# T245Controller_rev0.net
KiCad netlist of a schematic drawn in EAGLE
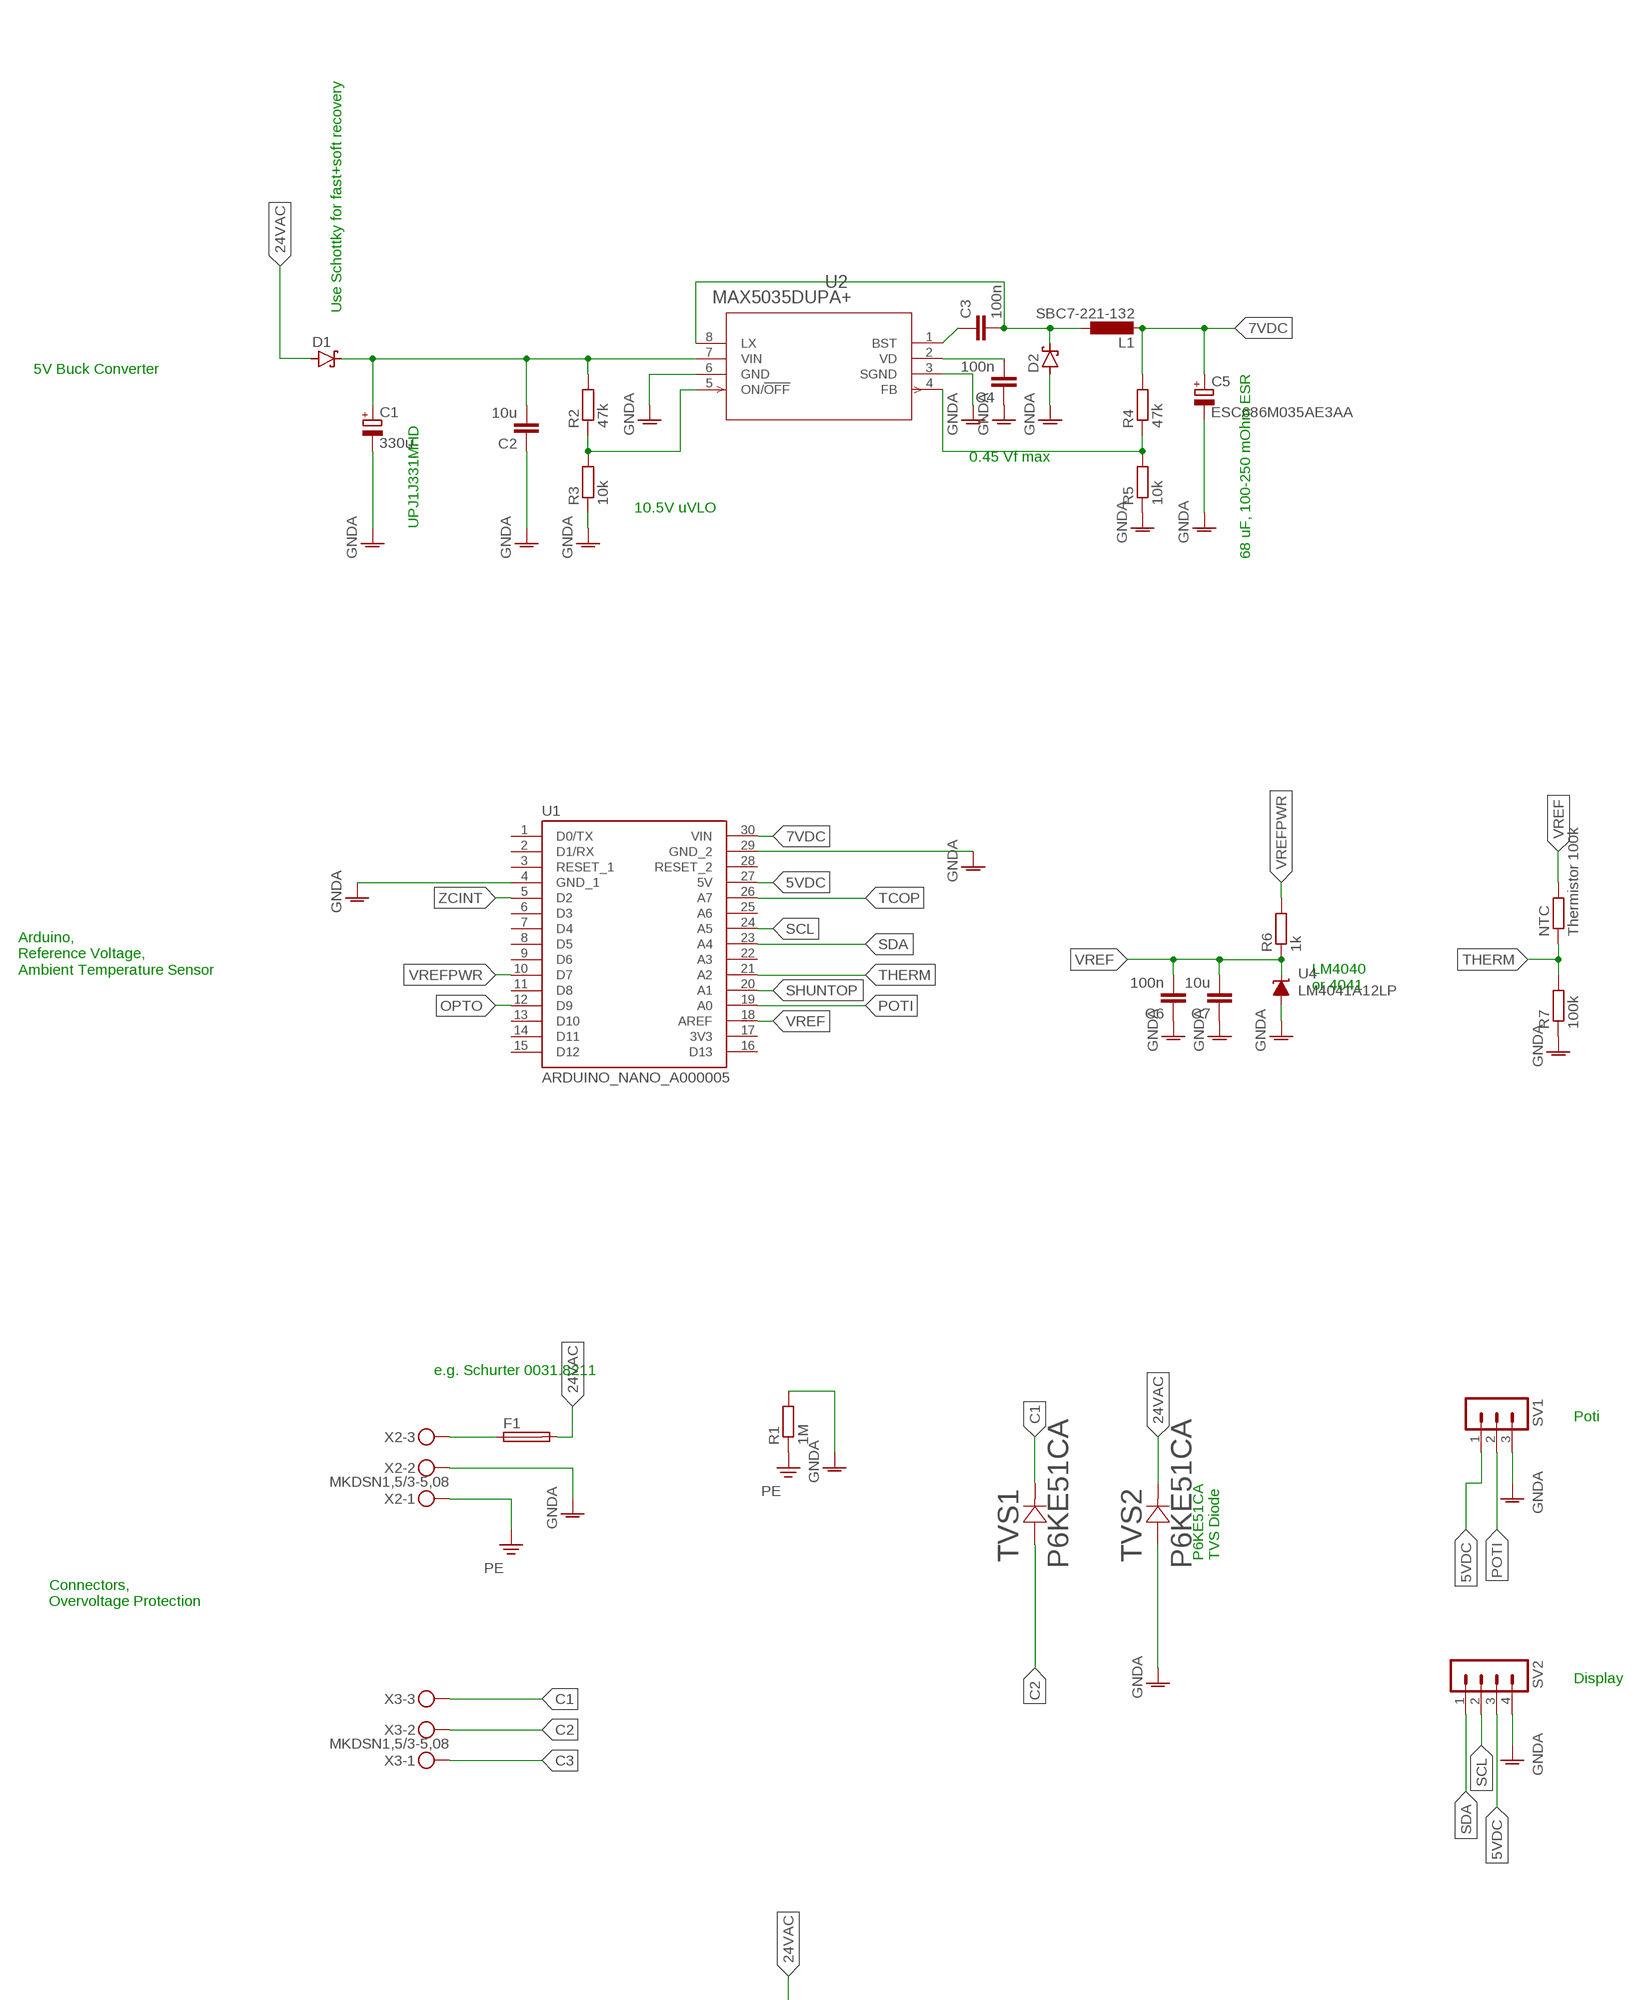
[diagram p0: schematic, sheet 1, part 1 of 2]
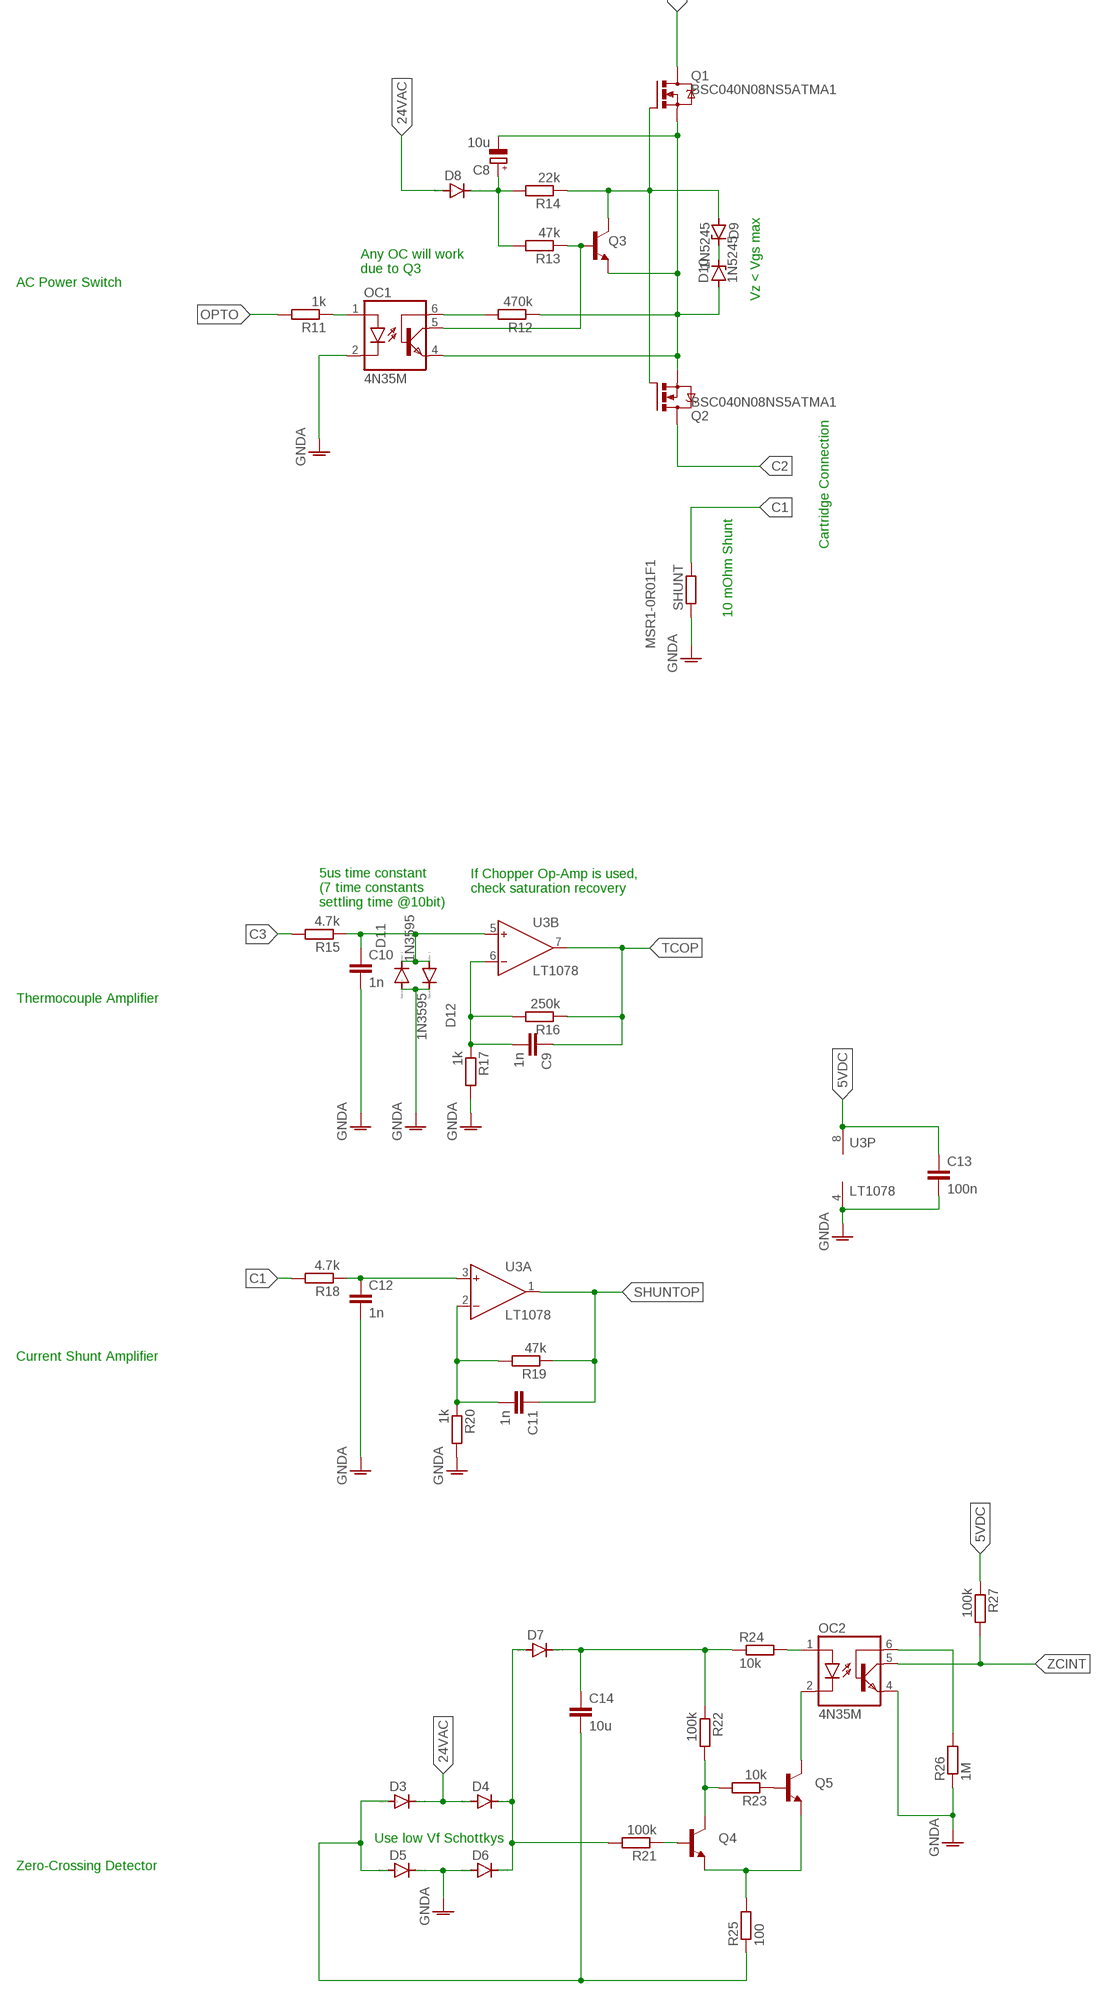
[diagram p1: schematic, sheet 1, part 2 of 2]

(export (version "E")
  (design (tool "Eeschema 10.0.6"))
  (components
    (comp (ref "C1")
      (value "330u")
      (footprint "eagle-import:E5-13")
      (libsource (lib "eagle-import") (part "CPOL-EUE5-13"))
    )
    (comp (ref "C2")
      (value "10u")
      (footprint "eagle-import:C050-024X044")
      (libsource (lib "eagle-import") (part "C-EU050-024X044"))
    )
    (comp (ref "C3")
      (value "100n")
      (footprint "eagle-import:C050-024X044")
      (libsource (lib "eagle-import") (part "C-EU050-024X044"))
    )
    (comp (ref "C4")
      (value "100n")
      (footprint "eagle-import:C050-024X044")
      (libsource (lib "eagle-import") (part "C-EU050-024X044"))
    )
    (comp (ref "C5")
      (value "ESC686M035AE3AA")
      (footprint "eagle-import:E2,5-6")
      (libsource (lib "eagle-import") (part "CPOL-EUE2.5-6"))
    )
    (comp (ref "C6")
      (value "100n")
      (footprint "eagle-import:C050-024X044")
      (libsource (lib "eagle-import") (part "C-EU050-024X044"))
    )
    (comp (ref "C7")
      (value "10u")
      (footprint "eagle-import:C050-024X044")
      (libsource (lib "eagle-import") (part "C-EU050-024X044"))
    )
    (comp (ref "C8")
      (value "10u")
      (footprint "eagle-import:E2,5-6")
      (libsource (lib "eagle-import") (part "CPOL-EUE2.5-6"))
    )
    (comp (ref "C9")
      (value "1n")
      (footprint "eagle-import:C050-024X044")
      (libsource (lib "eagle-import") (part "C-EU050-024X044"))
    )
    (comp (ref "C10")
      (value "1n")
      (footprint "eagle-import:C050-024X044")
      (libsource (lib "eagle-import") (part "C-EU050-024X044"))
    )
    (comp (ref "C11")
      (value "1n")
      (footprint "eagle-import:C050-024X044")
      (libsource (lib "eagle-import") (part "C-EU050-024X044"))
    )
    (comp (ref "C12")
      (value "1n")
      (footprint "eagle-import:C050-024X044")
      (libsource (lib "eagle-import") (part "C-EU050-024X044"))
    )
    (comp (ref "C13")
      (value "100n")
      (footprint "eagle-import:C050-024X044")
      (libsource (lib "eagle-import") (part "C-EU050-024X044"))
    )
    (comp (ref "C14")
      (value "10u")
      (footprint "eagle-import:C050-024X044")
      (libsource (lib "eagle-import") (part "C-EU050-024X044"))
    )
    (comp (ref "D1")
      (value "SCHOTTKY-DIODEF126Z12")
      (footprint "eagle-import:F126Z12")
      (libsource (lib "eagle-import") (part "SCHOTTKY-DIODEF126Z12"))
    )
    (comp (ref "D2")
      (value "SCHOTTKY-DIODEF126Z12")
      (footprint "eagle-import:F126Z12")
      (libsource (lib "eagle-import") (part "SCHOTTKY-DIODEF126Z12"))
    )
    (comp (ref "D3")
      (value "DIODE-D-7.5")
      (footprint "eagle-import:D-7.5")
      (libsource (lib "eagle-import") (part "DIODE-D-7.5"))
    )
    (comp (ref "D4")
      (value "DIODE-D-7.5")
      (footprint "eagle-import:D-7.5")
      (libsource (lib "eagle-import") (part "DIODE-D-7.5"))
    )
    (comp (ref "D5")
      (value "DIODE-D-7.5")
      (footprint "eagle-import:D-7.5")
      (libsource (lib "eagle-import") (part "DIODE-D-7.5"))
    )
    (comp (ref "D6")
      (value "DIODE-D-7.5")
      (footprint "eagle-import:D-7.5")
      (libsource (lib "eagle-import") (part "DIODE-D-7.5"))
    )
    (comp (ref "D7")
      (value "DIODE-D-7.5")
      (footprint "eagle-import:D-7.5")
      (libsource (lib "eagle-import") (part "DIODE-D-7.5"))
    )
    (comp (ref "D8")
      (value "DIODE-D-7.5")
      (footprint "eagle-import:D-7.5")
      (libsource (lib "eagle-import") (part "DIODE-D-7.5"))
    )
    (comp (ref "D9")
      (value "1N5245")
      (footprint "eagle-import:DO41Z10")
      (libsource (lib "eagle-import") (part "ZENER-DIODEDO41Z10"))
    )
    (comp (ref "D10")
      (value "1N5245")
      (footprint "eagle-import:DO41Z10")
      (libsource (lib "eagle-import") (part "ZENER-DIODEDO41Z10"))
    )
    (comp (ref "D11")
      (value "1N3595")
      (footprint "eagle-import:D-7.5")
      (libsource (lib "eagle-import") (part "DIODE-D-7.5"))
    )
    (comp (ref "D12")
      (value "1N3595")
      (footprint "eagle-import:D-7.5")
      (libsource (lib "eagle-import") (part "DIODE-D-7.5"))
    )
    (comp (ref "F1")
      (value "SH22,5A")
      (footprint "eagle-import:SH22,5A")
      (fields (field (name "MPN") "0031.7701.11"))
      (libsource (lib "eagle-import") (part "SH22,5A"))
    )
    (comp (ref "L1")
      (value "SBC7-221-132")
      (footprint "eagle-import:0207_10")
      (libsource (lib "eagle-import") (part "L-EU0207/10"))
    )
    (comp (ref "NTC")
      (value "Thermistor 100k")
      (footprint "eagle-import:0207_10")
      (libsource (lib "eagle-import") (part "rcl_334_R-EU_0207/10"))
    )
    (comp (ref "OC1")
      (value "4N35M")
      (footprint "eagle-import:DIL06")
      (fields (field (name "MPN") "4N35-M"))
      (libsource (lib "eagle-import") (part "4N?M35"))
    )
    (comp (ref "OC2")
      (value "4N35M")
      (footprint "eagle-import:DIL06")
      (fields (field (name "MPN") "4N35-M"))
      (libsource (lib "eagle-import") (part "4N?M35"))
    )
    (comp (ref "Q1")
      (value "BSC040N08NS5ATMA1")
      (footprint "eagle-import:TO220BV")
      (libsource (lib "eagle-import") (part "IRF540"))
    )
    (comp (ref "Q2")
      (value "BSC040N08NS5ATMA1")
      (footprint "eagle-import:TO220BV")
      (libsource (lib "eagle-import") (part "IRF540"))
    )
    (comp (ref "Q3")
      (value "2N5550-NPN-TO92-EBC")
      (footprint "eagle-import:TO92-EBC")
      (libsource (lib "eagle-import") (part "-NPN-TO92-EBC2N5550"))
    )
    (comp (ref "Q4")
      (value "2N5550-NPN-TO92-EBC")
      (footprint "eagle-import:TO92-EBC")
      (libsource (lib "eagle-import") (part "-NPN-TO92-EBC2N5550"))
    )
    (comp (ref "Q5")
      (value "2N5550-NPN-TO92-EBC")
      (footprint "eagle-import:TO92-EBC")
      (libsource (lib "eagle-import") (part "-NPN-TO92-EBC2N5550"))
    )
    (comp (ref "R1")
      (value "1M")
      (footprint "eagle-import:0207_10")
      (libsource (lib "eagle-import") (part "rcl_334_R-EU_0207/10"))
    )
    (comp (ref "R2")
      (value "47k")
      (footprint "eagle-import:0207_10")
      (libsource (lib "eagle-import") (part "rcl_334_R-EU_0207/10"))
    )
    (comp (ref "R3")
      (value "10k")
      (footprint "eagle-import:0207_10")
      (libsource (lib "eagle-import") (part "rcl_334_R-EU_0207/10"))
    )
    (comp (ref "R4")
      (value "47k")
      (footprint "eagle-import:0207_10")
      (libsource (lib "eagle-import") (part "rcl_334_R-EU_0207/10"))
    )
    (comp (ref "R5")
      (value "10k")
      (footprint "eagle-import:0207_10")
      (libsource (lib "eagle-import") (part "rcl_334_R-EU_0207/10"))
    )
    (comp (ref "R6")
      (value "1k")
      (footprint "eagle-import:0207_10")
      (libsource (lib "eagle-import") (part "rcl_334_R-EU_0207/10"))
    )
    (comp (ref "R7")
      (value "100k")
      (footprint "eagle-import:0207_10")
      (libsource (lib "eagle-import") (part "rcl_334_R-EU_0207/10"))
    )
    (comp (ref "R11")
      (value "1k")
      (footprint "eagle-import:0207_10")
      (libsource (lib "eagle-import") (part "rcl_334_R-EU_0207/10"))
    )
    (comp (ref "R12")
      (value "470k")
      (footprint "eagle-import:0207_10")
      (libsource (lib "eagle-import") (part "rcl_334_R-EU_0207/10"))
    )
    (comp (ref "R13")
      (value "47k")
      (footprint "eagle-import:0207_10")
      (libsource (lib "eagle-import") (part "rcl_334_R-EU_0207/10"))
    )
    (comp (ref "R14")
      (value "22k")
      (footprint "eagle-import:0207_10")
      (libsource (lib "eagle-import") (part "rcl_334_R-EU_0207/10"))
    )
    (comp (ref "R15")
      (value "4.7k")
      (footprint "eagle-import:0207_10")
      (libsource (lib "eagle-import") (part "rcl_334_R-EU_0207/10"))
    )
    (comp (ref "R16")
      (value "250k")
      (footprint "eagle-import:0207_10")
      (libsource (lib "eagle-import") (part "rcl_334_R-EU_0207/10"))
    )
    (comp (ref "R17")
      (value "1k")
      (footprint "eagle-import:0207_10")
      (libsource (lib "eagle-import") (part "rcl_334_R-EU_0207/10"))
    )
    (comp (ref "R18")
      (value "4.7k")
      (footprint "eagle-import:0207_10")
      (libsource (lib "eagle-import") (part "rcl_334_R-EU_0207/10"))
    )
    (comp (ref "R19")
      (value "47k")
      (footprint "eagle-import:0207_10")
      (libsource (lib "eagle-import") (part "rcl_334_R-EU_0207/10"))
    )
    (comp (ref "R20")
      (value "1k")
      (footprint "eagle-import:0207_10")
      (libsource (lib "eagle-import") (part "rcl_334_R-EU_0207/10"))
    )
    (comp (ref "R21")
      (value "100k")
      (footprint "eagle-import:0207_10")
      (libsource (lib "eagle-import") (part "rcl_334_R-EU_0207/10"))
    )
    (comp (ref "R22")
      (value "100k")
      (footprint "eagle-import:0207_10")
      (libsource (lib "eagle-import") (part "rcl_334_R-EU_0207/10"))
    )
    (comp (ref "R23")
      (value "10k")
      (footprint "eagle-import:0207_10")
      (libsource (lib "eagle-import") (part "rcl_334_R-EU_0207/10"))
    )
    (comp (ref "R24")
      (value "10k")
      (footprint "eagle-import:0207_10")
      (libsource (lib "eagle-import") (part "rcl_334_R-EU_0207/10"))
    )
    (comp (ref "R25")
      (value "100")
      (footprint "eagle-import:0207_10")
      (libsource (lib "eagle-import") (part "rcl_334_R-EU_0207/10"))
    )
    (comp (ref "R26")
      (value "1M")
      (footprint "eagle-import:0207_10")
      (libsource (lib "eagle-import") (part "rcl_334_R-EU_0207/10"))
    )
    (comp (ref "R27")
      (value "100k")
      (footprint "eagle-import:0207_10")
      (libsource (lib "eagle-import") (part "rcl_334_R-EU_0207/10"))
    )
    (comp (ref "SHUNT")
      (value "MSR1-0R01F1")
      (footprint "eagle-import:0207_12")
      (libsource (lib "eagle-import") (part "R-EU_0207/12"))
    )
    (comp (ref "SV1")
      (value "MA03-1")
      (footprint "eagle-import:MA03-1")
      (libsource (lib "eagle-import") (part "MA03-1"))
    )
    (comp (ref "SV2")
      (value "MA04-1")
      (footprint "eagle-import:MA04-1")
      (libsource (lib "eagle-import") (part "MA04-1"))
    )
    (comp (ref "TVS1")
      (value "P6KE51CA")
      (footprint "eagle-import:P6KESERIES_LTF")
      (libsource (lib "eagle-import") (part "P6KE51CA"))
    )
    (comp (ref "TVS2")
      (value "P6KE51CA")
      (footprint "eagle-import:P6KESERIES_LTF")
      (libsource (lib "eagle-import") (part "P6KE51CA"))
    )
    (comp (ref "U1")
      (value "ARDUINO_NANO_A000005")
      (footprint "eagle-import:MODULE_A000005")
      (fields (field (name "MF") "Arduino") (field (name "MP") "A000005"))
      (libsource (lib "eagle-import") (part "ARDUINO_NANO_A000005"))
    )
    (comp (ref "U2")
      (value "MAX5035DUPA+")
      (footprint "eagle-import:21-0043_P8+3_MXM")
      (fields (field (name "MANUFACTURER_PART_NUMBER") "max5035dupa+"))
      (libsource (lib "eagle-import") (part "MAX5035DUPA+"))
    )
    (comp (ref "U3")
      (value "LT1078")
      (footprint "eagle-import:DIL08")
      (libsource (lib "eagle-import") (part "AD8066N"))
    )
    (comp (ref "U4")
      (value "LM4041A12LP")
      (footprint "eagle-import:LP_O-PBCY-W3")
      (libsource (lib "eagle-import") (part "LM4041LPA12"))
    )
    (comp (ref "X2")
      (value "MKDSN1,5/3-5,08")
      (footprint "eagle-import:MKDSN1,5_3-5,08")
      (libsource (lib "eagle-import") (part "MKDSN1,5/3-5,08"))
    )
    (comp (ref "X3")
      (value "MKDSN1,5/3-5,08")
      (footprint "eagle-import:MKDSN1,5_3-5,08")
      (libsource (lib "eagle-import") (part "MKDSN1,5/3-5,08"))
    )
  )
  (nets
    (net (code "1") (name "3V3") (class "Default")
      (node (ref "U1") (pin "17") (pinfunction "3V3_17") (pintype "power_in"))
    )
    (net (code "2") (name "5VDC") (class "Default")
      (node (ref "C13") (pin "1") (pinfunction "1_1") (pintype "passive"))
      (node (ref "R27") (pin "1") (pinfunction "1_1") (pintype "passive"))
      (node (ref "SV1") (pin "1") (pinfunction "1_1") (pintype "passive"))
      (node (ref "SV2") (pin "3") (pinfunction "3_3") (pintype "passive"))
      (node (ref "U1") (pin "27") (pinfunction "5V_27") (pintype "power_in"))
      (node (ref "U3") (pin "8") (pinfunction "V+_8") (pintype "power_in"))
    )
    (net (code "3") (name "7VDC") (class "Default")
      (node (ref "C5") (pin "+") (pinfunction "+_+") (pintype "passive"))
      (node (ref "L1") (pin "2") (pinfunction "2_2") (pintype "passive"))
      (node (ref "R4") (pin "2") (pinfunction "2_2") (pintype "passive"))
      (node (ref "U1") (pin "30") (pinfunction "VIN_30") (pintype "power_in"))
    )
    (net (code "4") (name "24VAC") (class "Default")
      (node (ref "D1") (pin "A") (pinfunction "A_A") (pintype "passive"))
      (node (ref "D3") (pin "C") (pinfunction "C_C") (pintype "passive"))
      (node (ref "D4") (pin "A") (pinfunction "A_A") (pintype "passive"))
      (node (ref "D8") (pin "A") (pinfunction "A_A") (pintype "passive"))
      (node (ref "F1") (pin "2") (pinfunction "2_2") (pintype "passive"))
      (node (ref "Q1") (pin "D") (pinfunction "D_D") (pintype "passive"))
      (node (ref "TVS2") (pin "1") (pinfunction "11_1") (pintype "passive"))
    )
    (net (code "5") (name "C1") (class "Default")
      (node (ref "R18") (pin "2") (pinfunction "2_2") (pintype "passive"))
      (node (ref "SHUNT") (pin "2") (pinfunction "2_2") (pintype "passive"))
      (node (ref "TVS1") (pin "1") (pinfunction "11_1") (pintype "passive"))
      (node (ref "X3") (pin "3") (pinfunction "KL_3") (pintype "passive"))
    )
    (net (code "6") (name "C2") (class "Default")
      (node (ref "Q2") (pin "D") (pinfunction "D_D") (pintype "passive"))
      (node (ref "TVS1") (pin "2") (pinfunction "12_2") (pintype "passive"))
      (node (ref "X3") (pin "2") (pinfunction "KL_2") (pintype "passive"))
    )
    (net (code "7") (name "C3") (class "Default")
      (node (ref "R15") (pin "2") (pinfunction "2_2") (pintype "passive"))
      (node (ref "X3") (pin "1") (pinfunction "KL_1") (pintype "passive"))
    )
    (net (code "8") (name "GNDA") (class "Default")
      (node (ref "C1") (pin "-") (pinfunction "-_-") (pintype "passive"))
      (node (ref "C10") (pin "2") (pinfunction "2_2") (pintype "passive"))
      (node (ref "C12") (pin "2") (pinfunction "2_2") (pintype "passive"))
      (node (ref "C13") (pin "2") (pinfunction "2_2") (pintype "passive"))
      (node (ref "C2") (pin "1") (pinfunction "1_1") (pintype "passive"))
      (node (ref "C4") (pin "1") (pinfunction "1_1") (pintype "passive"))
      (node (ref "C5") (pin "-") (pinfunction "-_-") (pintype "passive"))
      (node (ref "C6") (pin "1") (pinfunction "1_1") (pintype "passive"))
      (node (ref "C7") (pin "1") (pinfunction "1_1") (pintype "passive"))
      (node (ref "D11") (pin "A") (pinfunction "A_A") (pintype "passive"))
      (node (ref "D12") (pin "C") (pinfunction "C_C") (pintype "passive"))
      (node (ref "D2") (pin "A") (pinfunction "A_A") (pintype "passive"))
      (node (ref "D5") (pin "C") (pinfunction "C_C") (pintype "passive"))
      (node (ref "D6") (pin "A") (pinfunction "A_A") (pintype "passive"))
      (node (ref "OC1") (pin "2") (pinfunction "C_2") (pintype "passive"))
      (node (ref "OC2") (pin "4") (pinfunction "EMI_4") (pintype "passive"))
      (node (ref "R1") (pin "2") (pinfunction "2_2") (pintype "passive"))
      (node (ref "R17") (pin "2") (pinfunction "2_2") (pintype "passive"))
      (node (ref "R20") (pin "2") (pinfunction "2_2") (pintype "passive"))
      (node (ref "R26") (pin "1") (pinfunction "1_1") (pintype "passive"))
      (node (ref "R3") (pin "1") (pinfunction "1_1") (pintype "passive"))
      (node (ref "R5") (pin "1") (pinfunction "1_1") (pintype "passive"))
      (node (ref "R7") (pin "1") (pinfunction "1_1") (pintype "passive"))
      (node (ref "SHUNT") (pin "1") (pinfunction "1_1") (pintype "passive"))
      (node (ref "SV1") (pin "3") (pinfunction "3_3") (pintype "passive"))
      (node (ref "SV2") (pin "4") (pinfunction "4_4") (pintype "passive"))
      (node (ref "TVS2") (pin "2") (pinfunction "12_2") (pintype "passive"))
      (node (ref "U1") (pin "29") (pinfunction "GND_2_29") (pintype "power_in"))
      (node (ref "U1") (pin "4") (pinfunction "GND_1_4") (pintype "power_in"))
      (node (ref "U2") (pin "3") (pinfunction "SGND_3") (pintype "power_in"))
      (node (ref "U2") (pin "6") (pinfunction "GND_6") (pintype "power_in"))
      (node (ref "U3") (pin "4") (pinfunction "V-_4") (pintype "power_in"))
      (node (ref "U4") (pin "3") (pinfunction "A_3") (pintype "passive"))
      (node (ref "X2") (pin "2") (pinfunction "KL_2") (pintype "passive"))
    )
    (net (code "9") (name "Net-(C8-Pad+)") (class "Default")
      (node (ref "C8") (pin "+") (pinfunction "+_+") (pintype "passive"))
      (node (ref "D8") (pin "C") (pinfunction "C_C") (pintype "passive"))
      (node (ref "R13") (pin "2") (pinfunction "2_2") (pintype "passive"))
      (node (ref "R14") (pin "2") (pinfunction "2_2") (pintype "passive"))
    )
    (net (code "10") (name "Net-(C14-Pad1)") (class "Default")
      (node (ref "C14") (pin "1") (pinfunction "1_1") (pintype "passive"))
      (node (ref "D7") (pin "C") (pinfunction "C_C") (pintype "passive"))
      (node (ref "R22") (pin "1") (pinfunction "1_1") (pintype "passive"))
      (node (ref "R24") (pin "1") (pinfunction "1_1") (pintype "passive"))
    )
    (net (code "11") (name "Net-(C14-Pad2)") (class "Default")
      (node (ref "C14") (pin "2") (pinfunction "2_2") (pintype "passive"))
      (node (ref "D3") (pin "A") (pinfunction "A_A") (pintype "passive"))
      (node (ref "D5") (pin "A") (pinfunction "A_A") (pintype "passive"))
      (node (ref "R25") (pin "1") (pinfunction "1_1") (pintype "passive"))
    )
    (net (code "12") (name "Net-(D4-PadC)") (class "Default")
      (node (ref "D4") (pin "C") (pinfunction "C_C") (pintype "passive"))
      (node (ref "D6") (pin "C") (pinfunction "C_C") (pintype "passive"))
      (node (ref "D7") (pin "A") (pinfunction "A_A") (pintype "passive"))
      (node (ref "R21") (pin "2") (pinfunction "2_2") (pintype "passive"))
    )
    (net (code "13") (name "Net-(D9-PadA)") (class "Default")
      (node (ref "D9") (pin "A") (pinfunction "A_A") (pintype "passive"))
      (node (ref "Q1") (pin "G") (pinfunction "G_G") (pintype "passive"))
      (node (ref "Q2") (pin "G") (pinfunction "G_G") (pintype "passive"))
      (node (ref "Q3") (pin "C") (pinfunction "C_C") (pintype "passive"))
      (node (ref "R14") (pin "1") (pinfunction "1_1") (pintype "passive"))
    )
    (net (code "14") (name "Net-(D10-PadC)") (class "Default")
      (node (ref "D10") (pin "C") (pinfunction "C_C") (pintype "passive"))
      (node (ref "D9") (pin "C") (pinfunction "C_C") (pintype "passive"))
    )
    (net (code "15") (name "Net-(OC1-A)") (class "Default")
      (node (ref "OC1") (pin "1") (pinfunction "A_1") (pintype "passive"))
      (node (ref "R11") (pin "1") (pinfunction "1_1") (pintype "passive"))
    )
    (net (code "16") (name "Net-(OC1-BAS)") (class "Default")
      (node (ref "OC1") (pin "6") (pinfunction "BAS_6") (pintype "passive"))
      (node (ref "R12") (pin "2") (pinfunction "2_2") (pintype "passive"))
    )
    (net (code "17") (name "Net-(OC1-COL)") (class "Default")
      (node (ref "OC1") (pin "5") (pinfunction "COL_5") (pintype "passive"))
      (node (ref "Q3") (pin "B") (pinfunction "B_B") (pintype "passive"))
      (node (ref "R13") (pin "1") (pinfunction "1_1") (pintype "passive"))
    )
    (net (code "18") (name "Net-(OC1-EMI)") (class "Default")
      (node (ref "C8") (pin "-") (pinfunction "-_-") (pintype "passive"))
      (node (ref "D10") (pin "A") (pinfunction "A_A") (pintype "passive"))
      (node (ref "OC1") (pin "4") (pinfunction "EMI_4") (pintype "passive"))
      (node (ref "Q1") (pin "S") (pinfunction "S_S") (pintype "passive"))
      (node (ref "Q2") (pin "S") (pinfunction "S_S") (pintype "passive"))
      (node (ref "Q3") (pin "E") (pinfunction "E_E") (pintype "passive"))
      (node (ref "R12") (pin "1") (pinfunction "1_1") (pintype "passive"))
    )
    (net (code "19") (name "Net-(OC2-A)") (class "Default")
      (node (ref "OC2") (pin "1") (pinfunction "A_1") (pintype "passive"))
      (node (ref "R24") (pin "2") (pinfunction "2_2") (pintype "passive"))
    )
    (net (code "20") (name "Net-(OC2-BAS)") (class "Default")
      (node (ref "OC2") (pin "6") (pinfunction "BAS_6") (pintype "passive"))
      (node (ref "R26") (pin "2") (pinfunction "2_2") (pintype "passive"))
    )
    (net (code "21") (name "Net-(OC2-C)") (class "Default")
      (node (ref "OC2") (pin "2") (pinfunction "C_2") (pintype "passive"))
      (node (ref "Q5") (pin "C") (pinfunction "C_C") (pintype "passive"))
    )
    (net (code "22") (name "Net-(Q4-PadB)") (class "Default")
      (node (ref "Q4") (pin "B") (pinfunction "B_B") (pintype "passive"))
      (node (ref "R21") (pin "1") (pinfunction "1_1") (pintype "passive"))
    )
    (net (code "23") (name "Net-(Q4-PadC)") (class "Default")
      (node (ref "Q4") (pin "C") (pinfunction "C_C") (pintype "passive"))
      (node (ref "R22") (pin "2") (pinfunction "2_2") (pintype "passive"))
      (node (ref "R23") (pin "2") (pinfunction "2_2") (pintype "passive"))
    )
    (net (code "24") (name "Net-(Q4-PadE)") (class "Default")
      (node (ref "Q4") (pin "E") (pinfunction "E_E") (pintype "passive"))
      (node (ref "Q5") (pin "E") (pinfunction "E_E") (pintype "passive"))
      (node (ref "R25") (pin "2") (pinfunction "2_2") (pintype "passive"))
    )
    (net (code "25") (name "Net-(Q5-PadB)") (class "Default")
      (node (ref "Q5") (pin "B") (pinfunction "B_B") (pintype "passive"))
      (node (ref "R23") (pin "1") (pinfunction "1_1") (pintype "passive"))
    )
    (net (code "26") (name "Net-(U2-BST)") (class "Default")
      (node (ref "C3") (pin "1") (pinfunction "1_1") (pintype "passive"))
      (node (ref "U2") (pin "1") (pinfunction "BST_1") (pintype "passive"))
    )
    (net (code "27") (name "Net-(U2-FB)") (class "Default")
      (node (ref "R4") (pin "1") (pinfunction "1_1") (pintype "passive"))
      (node (ref "R5") (pin "2") (pinfunction "2_2") (pintype "passive"))
      (node (ref "U2") (pin "4") (pinfunction "FB_4") (pintype "output"))
    )
    (net (code "28") (name "Net-(U2-LX)") (class "Default")
      (node (ref "C3") (pin "2") (pinfunction "2_2") (pintype "passive"))
      (node (ref "D2") (pin "C") (pinfunction "C_C") (pintype "passive"))
      (node (ref "L1") (pin "1") (pinfunction "1_1") (pintype "passive"))
      (node (ref "U2") (pin "8") (pinfunction "LX_8") (pintype "passive"))
    )
    (net (code "29") (name "Net-(U2-ON{slash}~{OFF})") (class "Default")
      (node (ref "R2") (pin "1") (pinfunction "1_1") (pintype "passive"))
      (node (ref "R3") (pin "2") (pinfunction "2_2") (pintype "passive"))
      (node (ref "U2") (pin "5") (pinfunction "ON/~{OFF}_5") (pintype "input"))
    )
    (net (code "30") (name "Net-(U2-VD)") (class "Default")
      (node (ref "C4") (pin "2") (pinfunction "2_2") (pintype "passive"))
      (node (ref "U2") (pin "2") (pinfunction "VD_2") (pintype "power_in"))
    )
    (net (code "31") (name "Net-(U2-VIN)") (class "Default")
      (node (ref "C1") (pin "+") (pinfunction "+_+") (pintype "passive"))
      (node (ref "C2") (pin "2") (pinfunction "2_2") (pintype "passive"))
      (node (ref "D1") (pin "C") (pinfunction "C_C") (pintype "passive"))
      (node (ref "R2") (pin "2") (pinfunction "2_2") (pintype "passive"))
      (node (ref "U2") (pin "7") (pinfunction "VIN_7") (pintype "power_in"))
    )
    (net (code "32") (name "Net-(U3A-IN+)") (class "Default")
      (node (ref "C12") (pin "1") (pinfunction "1_1") (pintype "passive"))
      (node (ref "R18") (pin "1") (pinfunction "1_1") (pintype "passive"))
      (node (ref "U3") (pin "3") (pinfunction "IN+_3") (pintype "input"))
    )
    (net (code "33") (name "Net-(U3A-IN-)") (class "Default")
      (node (ref "C11") (pin "2") (pinfunction "2_2") (pintype "passive"))
      (node (ref "R19") (pin "2") (pinfunction "2_2") (pintype "passive"))
      (node (ref "R20") (pin "1") (pinfunction "1_1") (pintype "passive"))
      (node (ref "U3") (pin "2") (pinfunction "IN-_2") (pintype "input"))
    )
    (net (code "34") (name "Net-(U3B-IN+)") (class "Default")
      (node (ref "C10") (pin "1") (pinfunction "1_1") (pintype "passive"))
      (node (ref "D11") (pin "C") (pinfunction "C_C") (pintype "passive"))
      (node (ref "D12") (pin "A") (pinfunction "A_A") (pintype "passive"))
      (node (ref "R15") (pin "1") (pinfunction "1_1") (pintype "passive"))
      (node (ref "U3") (pin "5") (pinfunction "IN+_5") (pintype "input"))
    )
    (net (code "35") (name "Net-(U3B-IN-)") (class "Default")
      (node (ref "C9") (pin "2") (pinfunction "2_2") (pintype "passive"))
      (node (ref "R16") (pin "2") (pinfunction "2_2") (pintype "passive"))
      (node (ref "R17") (pin "1") (pinfunction "1_1") (pintype "passive"))
      (node (ref "U3") (pin "6") (pinfunction "IN-_6") (pintype "input"))
    )
    (net (code "36") (name "Net-(X2C-KL)") (class "Default")
      (node (ref "F1") (pin "1") (pinfunction "1_1") (pintype "passive"))
      (node (ref "X2") (pin "3") (pinfunction "KL_3") (pintype "passive"))
    )
    (net (code "37") (name "OPTO") (class "Default")
      (node (ref "R11") (pin "2") (pinfunction "2_2") (pintype "passive"))
      (node (ref "U1") (pin "12") (pinfunction "D9_12") (pintype "bidirectional"))
    )
    (net (code "38") (name "PE") (class "Default")
      (node (ref "R1") (pin "1") (pinfunction "1_1") (pintype "passive"))
      (node (ref "X2") (pin "1") (pinfunction "KL_1") (pintype "passive"))
    )
    (net (code "39") (name "POTI") (class "Default")
      (node (ref "SV1") (pin "2") (pinfunction "2_2") (pintype "passive"))
      (node (ref "U1") (pin "19") (pinfunction "A0_19") (pintype "input"))
    )
    (net (code "40") (name "SCL") (class "Default")
      (node (ref "SV2") (pin "2") (pinfunction "2_2") (pintype "passive"))
      (node (ref "U1") (pin "24") (pinfunction "A5_24") (pintype "input"))
    )
    (net (code "41") (name "SDA") (class "Default")
      (node (ref "SV2") (pin "1") (pinfunction "1_1") (pintype "passive"))
      (node (ref "U1") (pin "23") (pinfunction "A4_23") (pintype "input"))
    )
    (net (code "42") (name "SHUNTOP") (class "Default")
      (node (ref "C11") (pin "1") (pinfunction "1_1") (pintype "passive"))
      (node (ref "R19") (pin "1") (pinfunction "1_1") (pintype "passive"))
      (node (ref "U1") (pin "20") (pinfunction "A1_20") (pintype "input"))
      (node (ref "U3") (pin "1") (pinfunction "OUT_1") (pintype "output"))
    )
    (net (code "43") (name "TCOP") (class "Default")
      (node (ref "C9") (pin "1") (pinfunction "1_1") (pintype "passive"))
      (node (ref "R16") (pin "1") (pinfunction "1_1") (pintype "passive"))
      (node (ref "U1") (pin "26") (pinfunction "A7_26") (pintype "input"))
      (node (ref "U3") (pin "7") (pinfunction "OUT_7") (pintype "output"))
    )
    (net (code "44") (name "THERM") (class "Default")
      (node (ref "NTC") (pin "1") (pinfunction "1_1") (pintype "passive"))
      (node (ref "R7") (pin "2") (pinfunction "2_2") (pintype "passive"))
      (node (ref "U1") (pin "21") (pinfunction "A2_21") (pintype "input"))
    )
    (net (code "45") (name "VREF") (class "Default")
      (node (ref "C6") (pin "2") (pinfunction "2_2") (pintype "passive"))
      (node (ref "C7") (pin "2") (pinfunction "2_2") (pintype "passive"))
      (node (ref "NTC") (pin "2") (pinfunction "2_2") (pintype "passive"))
      (node (ref "R6") (pin "1") (pinfunction "1_1") (pintype "passive"))
      (node (ref "U1") (pin "18") (pinfunction "AREF_18") (pintype "input"))
      (node (ref "U4") (pin "2") (pinfunction "C_2") (pintype "passive"))
    )
    (net (code "46") (name "VREFPWR") (class "Default")
      (node (ref "R6") (pin "2") (pinfunction "2_2") (pintype "passive"))
      (node (ref "U1") (pin "10") (pinfunction "D7_10") (pintype "bidirectional"))
    )
    (net (code "47") (name "ZCINT") (class "Default")
      (node (ref "OC2") (pin "5") (pinfunction "COL_5") (pintype "passive"))
      (node (ref "R27") (pin "2") (pinfunction "2_2") (pintype "passive"))
      (node (ref "U1") (pin "5") (pinfunction "D2_5") (pintype "bidirectional"))
    )
    (net (code "48") (name "unconnected-(U1-A3-Pad22)") (class "Default")
      (node (ref "U1") (pin "22") (pinfunction "A3_22") (pintype "input"))
    )
    (net (code "49") (name "unconnected-(U1-A6-Pad25)") (class "Default")
      (node (ref "U1") (pin "25") (pinfunction "A6_25") (pintype "input"))
    )
    (net (code "50") (name "unconnected-(U1-D0{slash}TX-Pad1)") (class "Default")
      (node (ref "U1") (pin "1") (pinfunction "D0/TX_1") (pintype "bidirectional"))
    )
    (net (code "51") (name "unconnected-(U1-D1{slash}RX-Pad2)") (class "Default")
      (node (ref "U1") (pin "2") (pinfunction "D1/RX_2") (pintype "bidirectional"))
    )
    (net (code "52") (name "unconnected-(U1-D3-Pad6)") (class "Default")
      (node (ref "U1") (pin "6") (pinfunction "D3_6") (pintype "bidirectional"))
    )
    (net (code "53") (name "unconnected-(U1-D4-Pad7)") (class "Default")
      (node (ref "U1") (pin "7") (pinfunction "D4_7") (pintype "bidirectional"))
    )
    (net (code "54") (name "unconnected-(U1-D5-Pad8)") (class "Default")
      (node (ref "U1") (pin "8") (pinfunction "D5_8") (pintype "bidirectional"))
    )
    (net (code "55") (name "unconnected-(U1-D6-Pad9)") (class "Default")
      (node (ref "U1") (pin "9") (pinfunction "D6_9") (pintype "bidirectional"))
    )
    (net (code "56") (name "unconnected-(U1-D8-Pad11)") (class "Default")
      (node (ref "U1") (pin "11") (pinfunction "D8_11") (pintype "bidirectional"))
    )
    (net (code "57") (name "unconnected-(U1-D10-Pad13)") (class "Default")
      (node (ref "U1") (pin "13") (pinfunction "D10_13") (pintype "bidirectional"))
    )
    (net (code "58") (name "unconnected-(U1-D11-Pad14)") (class "Default")
      (node (ref "U1") (pin "14") (pinfunction "D11_14") (pintype "bidirectional"))
    )
    (net (code "59") (name "unconnected-(U1-D12-Pad15)") (class "Default")
      (node (ref "U1") (pin "15") (pinfunction "D12_15") (pintype "bidirectional"))
    )
    (net (code "60") (name "unconnected-(U1-D13-Pad16)") (class "Default")
      (node (ref "U1") (pin "16") (pinfunction "D13_16") (pintype "bidirectional"))
    )
    (net (code "61") (name "unconnected-(U1-RESET_1-Pad3)") (class "Default")
      (node (ref "U1") (pin "3") (pinfunction "RESET_1_3") (pintype "input"))
    )
    (net (code "62") (name "unconnected-(U1-RESET_2-Pad28)") (class "Default")
      (node (ref "U1") (pin "28") (pinfunction "RESET_2_28") (pintype "input"))
    )
  )
)
